# NodeMLX.net
KiCad netlist of a schematic drawn in EAGLE
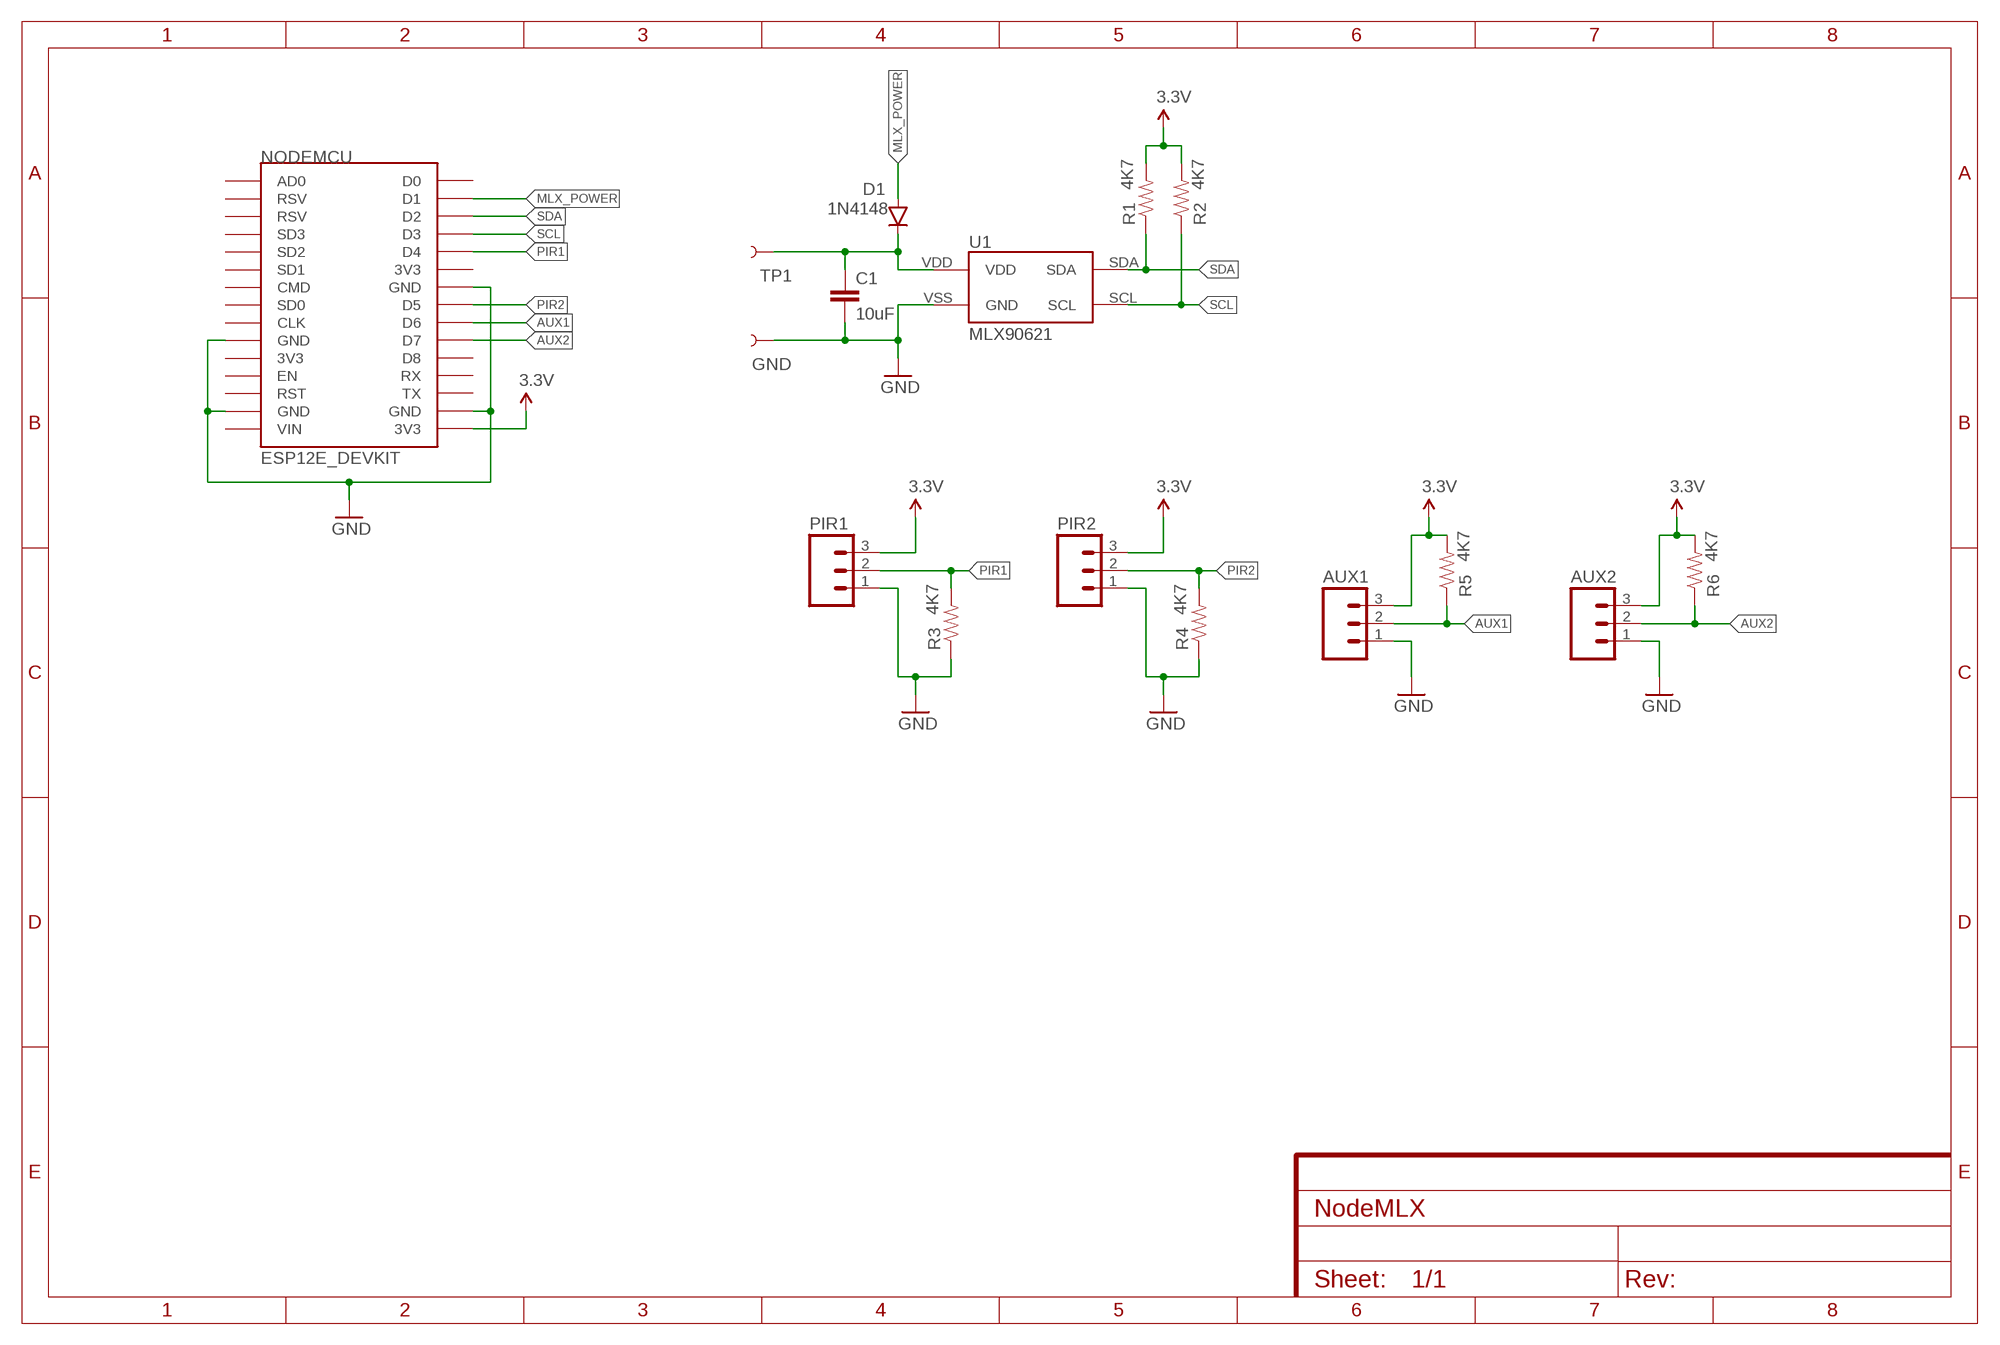
[diagram p0: schematic, sheet 1, part 1 of 2]
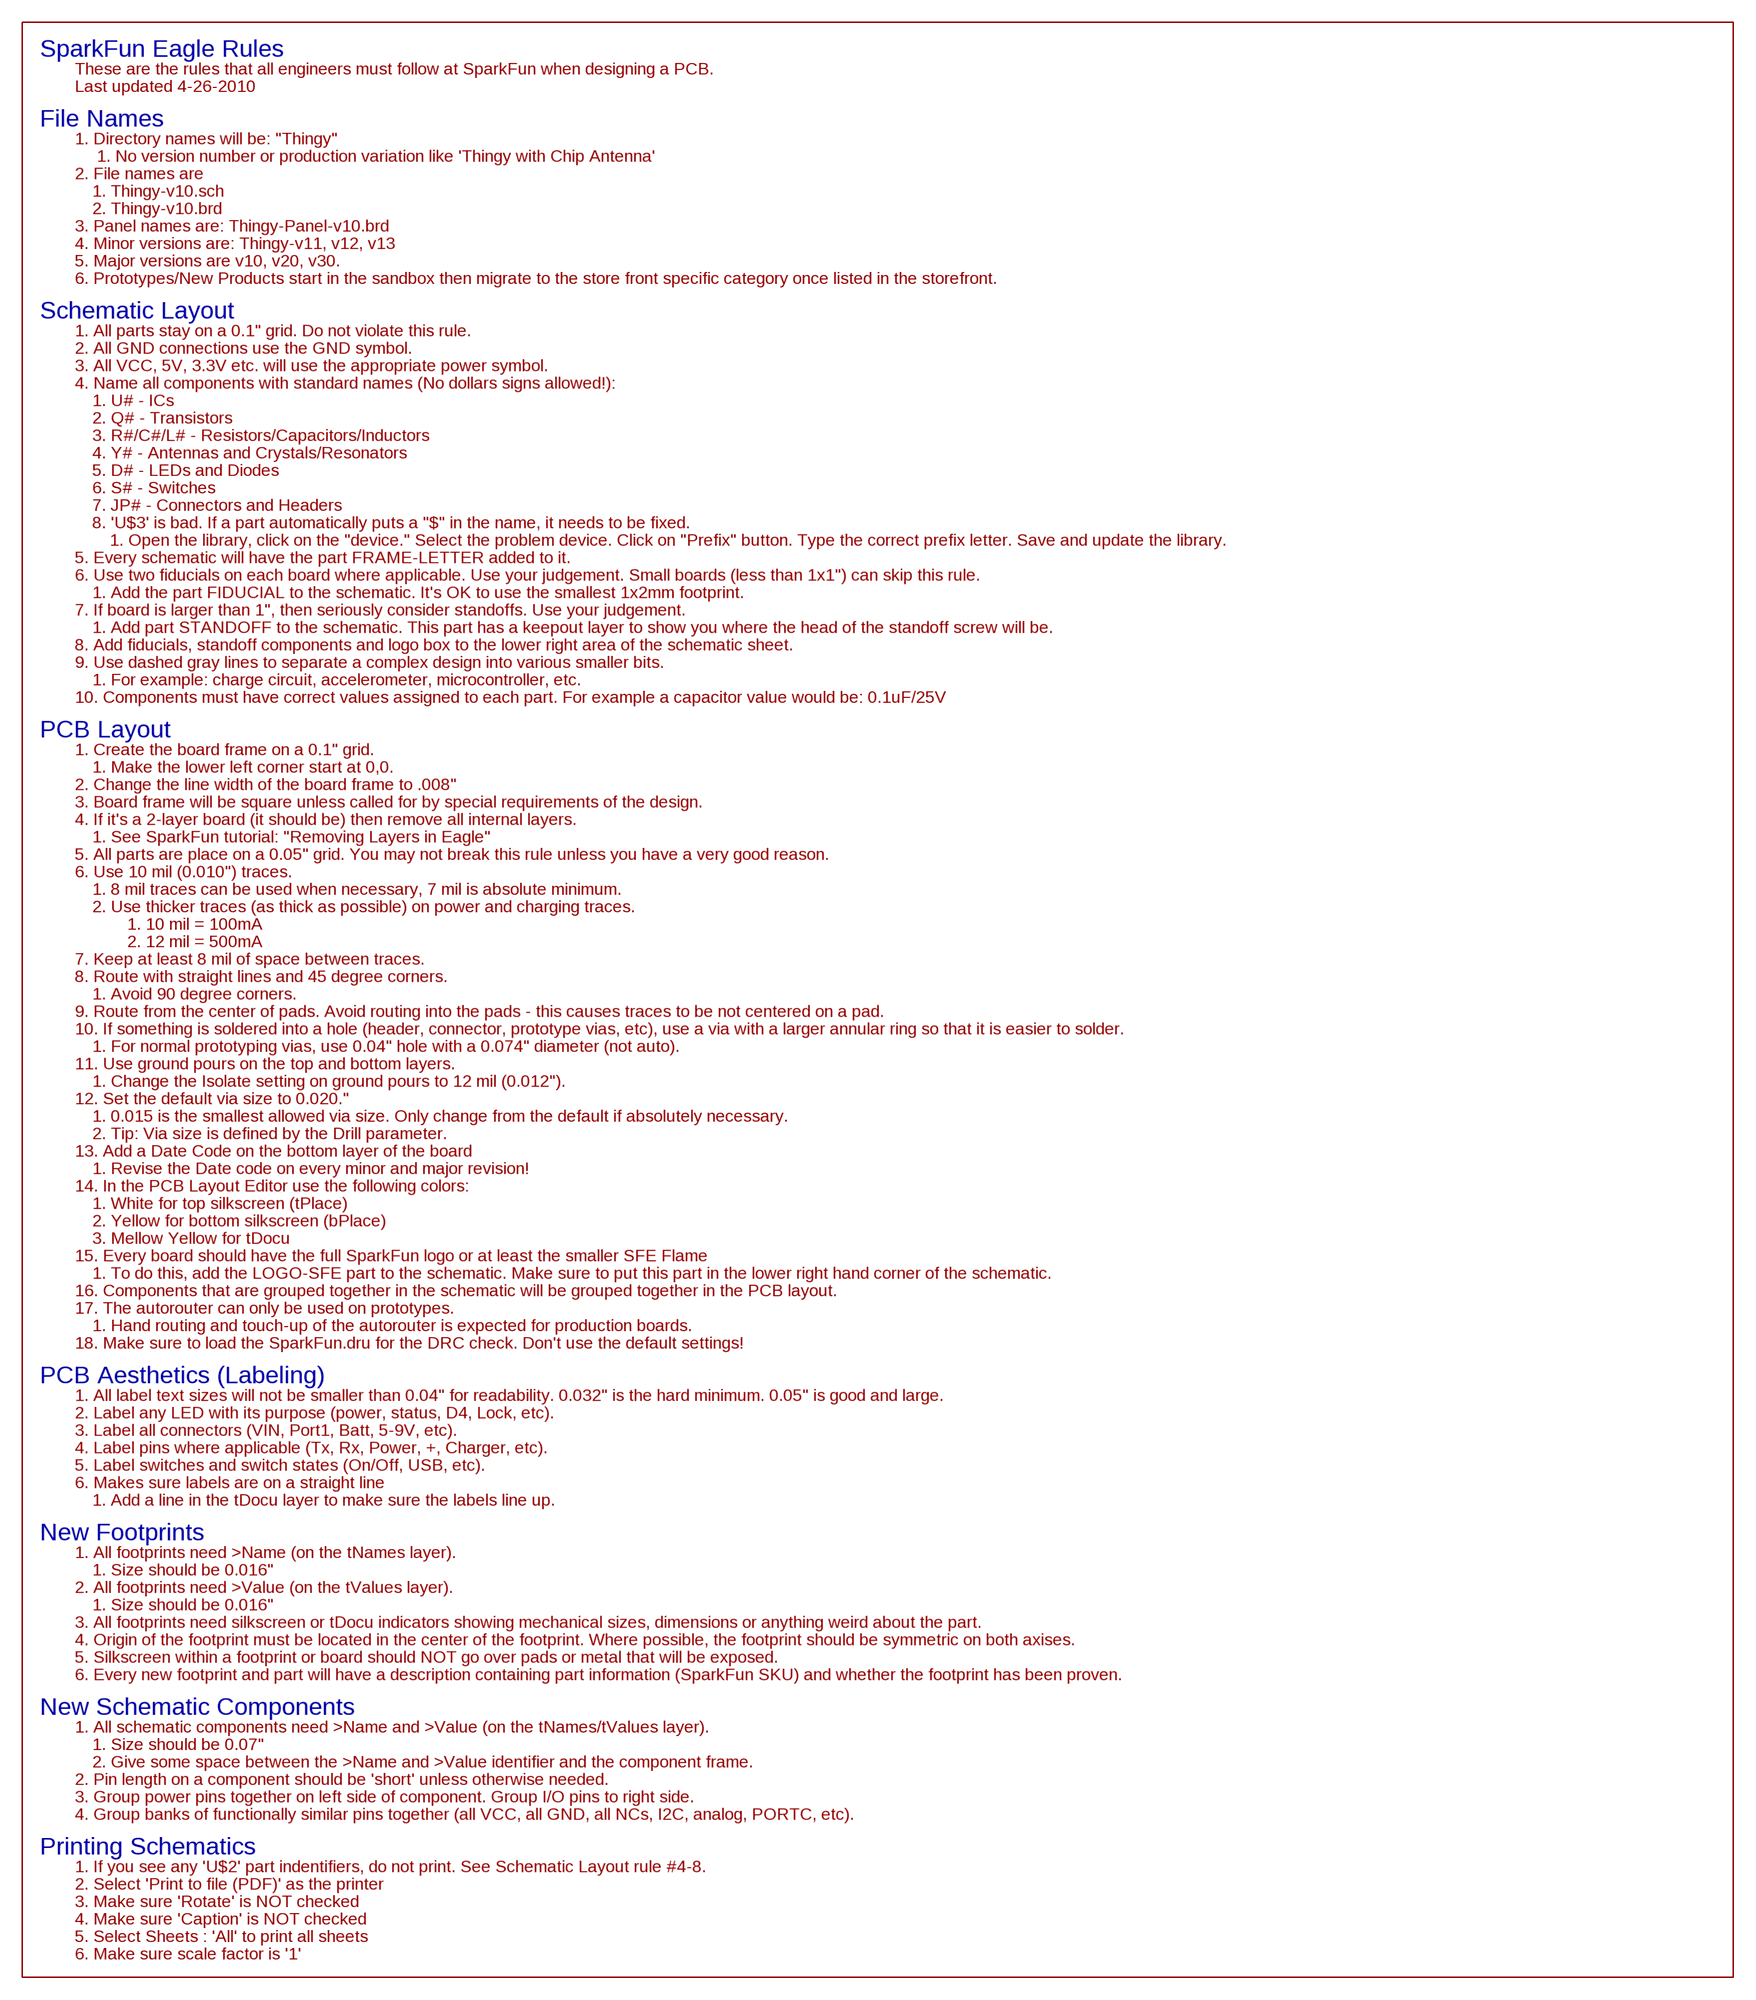
[diagram p1: schematic, sheet 1, part 2 of 2]

(export (version "E")
  (design (tool "Eeschema 10.0.6"))
  (components
    (comp (ref "AUX1")
      (value "M03PTH")
      (footprint "eagle-import:1X03")
      (libsource (lib "eagle-import") (part "M03PTH"))
    )
    (comp (ref "AUX2")
      (value "M03PTH")
      (footprint "eagle-import:1X03")
      (libsource (lib "eagle-import") (part "M03PTH"))
    )
    (comp (ref "C1")
      (value "10uF")
      (footprint "eagle-import:1206")
      (libsource (lib "eagle-import") (part "CAP1206"))
    )
    (comp (ref "D1")
      (value "1N4148")
      (footprint "eagle-import:SOD-323")
      (libsource (lib "eagle-import") (part "DIODEBAS16"))
    )
    (comp (ref "GND")
      (value "TEST-POINTTP_15TH_THRU")
      (footprint "eagle-import:TP_15TH")
      (libsource (lib "eagle-import") (part "TEST-POINTTP_15TH_THRU"))
    )
    (comp (ref "NODEMCU")
      (value "ESP12E_DEVKIT")
      (footprint "eagle-import:ESP12E_DEVKIT")
      (libsource (lib "eagle-import") (part "ESP12E_DEVKIT"))
    )
    (comp (ref "PIR1")
      (value "M03PTH")
      (footprint "eagle-import:1X03")
      (libsource (lib "eagle-import") (part "M03PTH"))
    )
    (comp (ref "PIR2")
      (value "M03PTH")
      (footprint "eagle-import:1X03")
      (libsource (lib "eagle-import") (part "M03PTH"))
    )
    (comp (ref "R1")
      (value "4K7")
      (footprint "eagle-import:1206")
      (libsource (lib "eagle-import") (part "RESISTOR1206"))
    )
    (comp (ref "R2")
      (value "4K7")
      (footprint "eagle-import:1206")
      (libsource (lib "eagle-import") (part "RESISTOR1206"))
    )
    (comp (ref "R3")
      (value "4K7")
      (footprint "eagle-import:1206")
      (libsource (lib "eagle-import") (part "RESISTOR1206"))
    )
    (comp (ref "R4")
      (value "4K7")
      (footprint "eagle-import:1206")
      (libsource (lib "eagle-import") (part "RESISTOR1206"))
    )
    (comp (ref "R5")
      (value "4K7")
      (footprint "eagle-import:1206")
      (libsource (lib "eagle-import") (part "RESISTOR1206"))
    )
    (comp (ref "R6")
      (value "4K7")
      (footprint "eagle-import:1206")
      (libsource (lib "eagle-import") (part "RESISTOR1206"))
    )
    (comp (ref "TP1")
      (value "TEST-POINTTP_15TH_THRU")
      (footprint "eagle-import:TP_15TH")
      (libsource (lib "eagle-import") (part "TEST-POINTTP_15TH_THRU"))
    )
    (comp (ref "U1")
      (value "MLX90621")
      (footprint "eagle-import:MLX90621")
      (libsource (lib "eagle-import") (part "MLX90621"))
    )
  )
  (nets
    (net (code "1") (name "3.3V") (class "Default")
      (node (ref "AUX1") (pin "3") (pinfunction "3_3") (pintype "passive"))
      (node (ref "AUX2") (pin "3") (pinfunction "3_3") (pintype "passive"))
      (node (ref "NODEMCU") (pin "3V3@2") (pinfunction "3V3_3V3@2") (pintype "bidirectional"))
      (node (ref "PIR1") (pin "3") (pinfunction "3_3") (pintype "passive"))
      (node (ref "PIR2") (pin "3") (pinfunction "3_3") (pintype "passive"))
      (node (ref "R1") (pin "2") (pinfunction "2_2") (pintype "passive"))
      (node (ref "R2") (pin "2") (pinfunction "2_2") (pintype "passive"))
      (node (ref "R5") (pin "2") (pinfunction "2_2") (pintype "passive"))
      (node (ref "R6") (pin "2") (pinfunction "2_2") (pintype "passive"))
    )
    (net (code "2") (name "AUX1") (class "Default")
      (node (ref "AUX1") (pin "2") (pinfunction "2_2") (pintype "passive"))
      (node (ref "NODEMCU") (pin "D6") (pinfunction "D6_D6") (pintype "bidirectional"))
      (node (ref "R5") (pin "1") (pinfunction "1_1") (pintype "passive"))
    )
    (net (code "3") (name "AUX2") (class "Default")
      (node (ref "AUX2") (pin "2") (pinfunction "2_2") (pintype "passive"))
      (node (ref "NODEMCU") (pin "D7") (pinfunction "D7_D7") (pintype "bidirectional"))
      (node (ref "R6") (pin "1") (pinfunction "1_1") (pintype "passive"))
    )
    (net (code "4") (name "GND") (class "Default")
      (node (ref "AUX1") (pin "1") (pinfunction "1_1") (pintype "passive"))
      (node (ref "AUX2") (pin "1") (pinfunction "1_1") (pintype "passive"))
      (node (ref "C1") (pin "2") (pinfunction "2_2") (pintype "passive"))
      (node (ref "GND") (pin "P$1") (pinfunction "1_P$1") (pintype "bidirectional"))
      (node (ref "NODEMCU") (pin "GND@0") (pinfunction "GND_GND@0") (pintype "bidirectional"))
      (node (ref "NODEMCU") (pin "GND@1") (pinfunction "GND_GND@1") (pintype "bidirectional"))
      (node (ref "NODEMCU") (pin "GND@2") (pinfunction "GND_GND@2") (pintype "bidirectional"))
      (node (ref "NODEMCU") (pin "GND@3") (pinfunction "GND_GND@3") (pintype "bidirectional"))
      (node (ref "PIR1") (pin "1") (pinfunction "1_1") (pintype "passive"))
      (node (ref "PIR2") (pin "1") (pinfunction "1_1") (pintype "passive"))
      (node (ref "R3") (pin "1") (pinfunction "1_1") (pintype "passive"))
      (node (ref "R4") (pin "1") (pinfunction "1_1") (pintype "passive"))
      (node (ref "U1") (pin "VSS") (pinfunction "GND_VSS") (pintype "power_in"))
    )
    (net (code "5") (name "MLX_POWER") (class "Default")
      (node (ref "D1") (pin "A") (pinfunction "A_A") (pintype "passive"))
      (node (ref "NODEMCU") (pin "D1") (pinfunction "D1_D1") (pintype "bidirectional"))
    )
    (net (code "6") (name "Net-(TP1-1)") (class "Default")
      (node (ref "C1") (pin "1") (pinfunction "1_1") (pintype "passive"))
      (node (ref "D1") (pin "C") (pinfunction "C_C") (pintype "passive"))
      (node (ref "TP1") (pin "P$1") (pinfunction "1_P$1") (pintype "bidirectional"))
      (node (ref "U1") (pin "VDD") (pinfunction "VDD_VDD") (pintype "power_in"))
    )
    (net (code "7") (name "PIR1") (class "Default")
      (node (ref "NODEMCU") (pin "D4") (pinfunction "D4_D4") (pintype "bidirectional"))
      (node (ref "PIR1") (pin "2") (pinfunction "2_2") (pintype "passive"))
      (node (ref "R3") (pin "2") (pinfunction "2_2") (pintype "passive"))
    )
    (net (code "8") (name "PIR2") (class "Default")
      (node (ref "NODEMCU") (pin "D5") (pinfunction "D5_D5") (pintype "bidirectional"))
      (node (ref "PIR2") (pin "2") (pinfunction "2_2") (pintype "passive"))
      (node (ref "R4") (pin "2") (pinfunction "2_2") (pintype "passive"))
    )
    (net (code "9") (name "SCL") (class "Default")
      (node (ref "NODEMCU") (pin "D3") (pinfunction "D3_D3") (pintype "bidirectional"))
      (node (ref "R2") (pin "1") (pinfunction "1_1") (pintype "passive"))
      (node (ref "U1") (pin "SCL") (pinfunction "SCL_SCL") (pintype "bidirectional"))
    )
    (net (code "10") (name "SDA") (class "Default")
      (node (ref "NODEMCU") (pin "D2") (pinfunction "D2_D2") (pintype "bidirectional"))
      (node (ref "R1") (pin "1") (pinfunction "1_1") (pintype "passive"))
      (node (ref "U1") (pin "SDA") (pinfunction "SDA_SDA") (pintype "bidirectional"))
    )
    (net (code "11") (name "unconnected-(NODEMCU-3V3-Pad3V3@0)") (class "Default")
      (node (ref "NODEMCU") (pin "3V3@0") (pinfunction "3V3_3V3@0") (pintype "bidirectional"))
    )
    (net (code "12") (name "unconnected-(NODEMCU-3V3-Pad3V3@1)") (class "Default")
      (node (ref "NODEMCU") (pin "3V3@1") (pinfunction "3V3_3V3@1") (pintype "bidirectional"))
    )
    (net (code "13") (name "unconnected-(NODEMCU-PadAD0)") (class "Default")
      (node (ref "NODEMCU") (pin "AD0") (pinfunction "AD0_AD0") (pintype "bidirectional"))
    )
    (net (code "14") (name "unconnected-(NODEMCU-PadCLK)") (class "Default")
      (node (ref "NODEMCU") (pin "CLK") (pinfunction "CLK_CLK") (pintype "bidirectional"))
    )
    (net (code "15") (name "unconnected-(NODEMCU-PadCMD)") (class "Default")
      (node (ref "NODEMCU") (pin "CMD") (pinfunction "CMD_CMD") (pintype "bidirectional"))
    )
    (net (code "16") (name "unconnected-(NODEMCU-PadD0)") (class "Default")
      (node (ref "NODEMCU") (pin "D0") (pinfunction "D0_D0") (pintype "bidirectional"))
    )
    (net (code "17") (name "unconnected-(NODEMCU-PadD8)") (class "Default")
      (node (ref "NODEMCU") (pin "D8") (pinfunction "D8_D8") (pintype "bidirectional"))
    )
    (net (code "18") (name "unconnected-(NODEMCU-PadEN)") (class "Default")
      (node (ref "NODEMCU") (pin "EN") (pinfunction "EN_EN") (pintype "bidirectional"))
    )
    (net (code "19") (name "unconnected-(NODEMCU-PadRST)") (class "Default")
      (node (ref "NODEMCU") (pin "RST") (pinfunction "RST_RST") (pintype "bidirectional"))
    )
    (net (code "20") (name "unconnected-(NODEMCU-PadRX)") (class "Default")
      (node (ref "NODEMCU") (pin "RX") (pinfunction "RX_RX") (pintype "bidirectional"))
    )
    (net (code "21") (name "unconnected-(NODEMCU-PadSD0)") (class "Default")
      (node (ref "NODEMCU") (pin "SD0") (pinfunction "SD0_SD0") (pintype "bidirectional"))
    )
    (net (code "22") (name "unconnected-(NODEMCU-PadSD1)") (class "Default")
      (node (ref "NODEMCU") (pin "SD1") (pinfunction "SD1_SD1") (pintype "bidirectional"))
    )
    (net (code "23") (name "unconnected-(NODEMCU-PadSD2)") (class "Default")
      (node (ref "NODEMCU") (pin "SD2") (pinfunction "SD2_SD2") (pintype "bidirectional"))
    )
    (net (code "24") (name "unconnected-(NODEMCU-PadSD3)") (class "Default")
      (node (ref "NODEMCU") (pin "SD3") (pinfunction "SD3_SD3") (pintype "bidirectional"))
    )
    (net (code "25") (name "unconnected-(NODEMCU-PadTX)") (class "Default")
      (node (ref "NODEMCU") (pin "TX") (pinfunction "TX_TX") (pintype "bidirectional"))
    )
    (net (code "26") (name "unconnected-(NODEMCU-PadVIN)") (class "Default")
      (node (ref "NODEMCU") (pin "VIN") (pinfunction "VIN_VIN") (pintype "bidirectional"))
    )
    (net (code "27") (name "unconnected-(NODEMCU-RSV-PadRSV@0)") (class "Default")
      (node (ref "NODEMCU") (pin "RSV@0") (pinfunction "RSV_RSV@0") (pintype "bidirectional"))
    )
    (net (code "28") (name "unconnected-(NODEMCU-RSV-PadRSV@1)") (class "Default")
      (node (ref "NODEMCU") (pin "RSV@1") (pinfunction "RSV_RSV@1") (pintype "bidirectional"))
    )
  )
)
